# USB-PROG-UART.net
KiCad netlist of a schematic drawn in Altium Designer
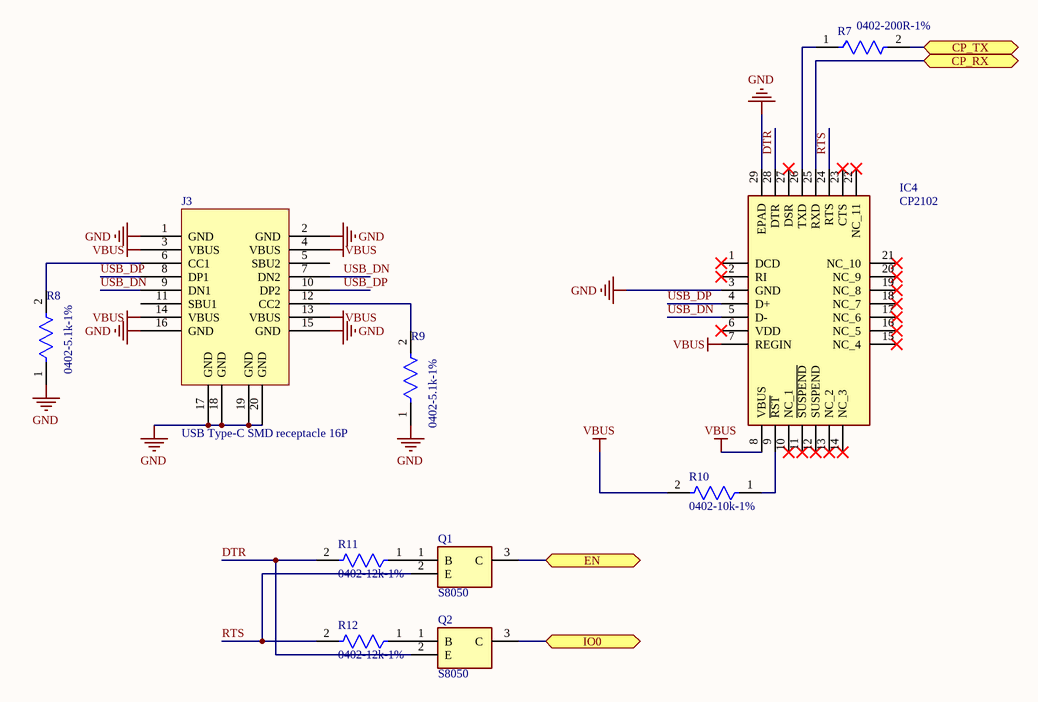
[diagram p0: USB-PROG-UART.SchDoc]

(export (version "E")
  (design (tool "Eeschema 10.0.6"))
  (components
    (comp (ref "IC4")
      (value "CP2102")
      (footprint "SamacSys:QFN50P500X500X100-29N-D")
      (description "Integrated Circuit")
      (fields (field (name "MOUSER PART NUMBER") "634-CP2102"))
      (libsource (lib "SamacSys") (part "CP2102"))
    )
    (comp (ref "J3")
      (value "USB Type-C SMD receptacle 16P")
      (footprint "USB Type-C SMD receptacle 16P")
      (libsource (lib "myLib") (part "USB Type-C SMD receptacle 16P"))
    )
    (comp (ref "Q1")
      (value "S8050")
      (footprint "SamacSys:SOT95P240X115-3N")
      (description "Transistor")
      (libsource (lib "SamacSys") (part "S8050"))
    )
    (comp (ref "Q2")
      (value "S8050")
      (footprint "SamacSys:SOT95P240X115-3N")
      (description "Transistor")
      (libsource (lib "*") (part "S8050"))
    )
    (comp (ref "R7")
      (value "0402-200R-1%")
      (footprint "FP-CRCW0402-e3-IPC_C")
      (description "RES Thick Film, 0Ω, 0.063W, 0402")
      (fields (field (name "TOLERANCE") "5%"))
      (libsource (lib "Altium Content Vault") (part "1029c3af85768c4190bb7ad29bc67b5"))
    )
    (comp (ref "R8")
      (value "0402-5.1k-1%")
      (footprint "FP-CRCW0402-e3-IPC_C")
      (description "RES Thick Film, 0Ω, 0.063W, 0402")
      (fields (field (name "TOLERANCE") "5%"))
      (libsource (lib "Altium Content Vault") (part "1029c3af85768c4190bb7ad29bc67b5"))
    )
    (comp (ref "R9")
      (value "0402-5.1k-1%")
      (footprint "FP-CRCW0402-e3-IPC_C")
      (description "RES Thick Film, 0Ω, 0.063W, 0402")
      (fields (field (name "TOLERANCE") "5%"))
      (libsource (lib "Altium Content Vault") (part "1029c3af85768c4190bb7ad29bc67b5"))
    )
    (comp (ref "R10")
      (value "0402-10k-1%")
      (footprint "FP-CRCW0402-e3-IPC_C")
      (description "RES Thick Film, 0Ω, 0.063W, 0402")
      (fields (field (name "TOLERANCE") "5%"))
      (libsource (lib "Altium Content Vault") (part "1029c3af85768c4190bb7ad29bc67b5"))
    )
    (comp (ref "R11")
      (value "0402-12k-1%")
      (footprint "FP-CRCW0402-e3-IPC_C")
      (description "RES Thick Film, 0Ω, 0.063W, 0402")
      (fields (field (name "TOLERANCE") "5%"))
      (libsource (lib "Altium Content Vault") (part "1029c3af85768c4190bb7ad29bc67b5"))
    )
    (comp (ref "R12")
      (value "0402-12k-1%")
      (footprint "FP-CRCW0402-e3-IPC_C")
      (description "RES Thick Film, 0Ω, 0.063W, 0402")
      (fields (field (name "TOLERANCE") "5%"))
      (libsource (lib "Altium Content Vault") (part "1029c3af85768c4190bb7ad29bc67b5"))
    )
  )
  (nets
    (net (code "1") (name "/CP_RX") (class "Default")
      (node (ref "IC4") (pin "25") (pinfunction "RXD_25") (pintype "passive"))
    )
    (net (code "2") (name "/CP_TX") (class "Default")
      (node (ref "R7") (pin "2") (pinfunction "2_2") (pintype "passive"))
    )
    (net (code "3") (name "/DTR") (class "Default")
      (node (ref "IC4") (pin "28") (pinfunction "DTR_28") (pintype "passive"))
      (node (ref "Q2") (pin "2") (pinfunction "E_2") (pintype "passive"))
      (node (ref "R11") (pin "2") (pinfunction "2_2") (pintype "passive"))
    )
    (net (code "4") (name "/EN") (class "Default")
      (node (ref "Q1") (pin "3") (pinfunction "C_3") (pintype "passive"))
    )
    (net (code "5") (name "/IO0") (class "Default")
      (node (ref "Q2") (pin "3") (pinfunction "C_3") (pintype "passive"))
    )
    (net (code "6") (name "/RTS") (class "Default")
      (node (ref "IC4") (pin "24") (pinfunction "RTS_24") (pintype "passive"))
      (node (ref "Q1") (pin "2") (pinfunction "E_2") (pintype "passive"))
      (node (ref "R12") (pin "2") (pinfunction "2_2") (pintype "passive"))
    )
    (net (code "7") (name "/USB_DN") (class "Default")
      (node (ref "IC4") (pin "5") (pinfunction "D-_5") (pintype "passive"))
      (node (ref "J3") (pin "7") (pinfunction "DN2_7") (pintype "passive"))
      (node (ref "J3") (pin "9") (pinfunction "DN1_9") (pintype "passive"))
    )
    (net (code "8") (name "/USB_DP") (class "Default")
      (node (ref "IC4") (pin "4") (pinfunction "D+_4") (pintype "passive"))
      (node (ref "J3") (pin "10") (pinfunction "DP2_10") (pintype "passive"))
      (node (ref "J3") (pin "8") (pinfunction "DP1_8") (pintype "passive"))
    )
    (net (code "9") (name "GND") (class "Default")
      (node (ref "IC4") (pin "29") (pinfunction "EPAD_29") (pintype "passive"))
      (node (ref "IC4") (pin "3") (pinfunction "GND_3") (pintype "passive"))
      (node (ref "J3") (pin "1") (pinfunction "GND_1") (pintype "passive"))
      (node (ref "J3") (pin "15") (pinfunction "GND_15") (pintype "passive"))
      (node (ref "J3") (pin "16") (pinfunction "GND_16") (pintype "passive"))
      (node (ref "J3") (pin "17") (pinfunction "GND_17") (pintype "passive"))
      (node (ref "J3") (pin "18") (pinfunction "GND_18") (pintype "passive"))
      (node (ref "J3") (pin "19") (pinfunction "GND_19") (pintype "passive"))
      (node (ref "J3") (pin "2") (pinfunction "GND_2") (pintype "passive"))
      (node (ref "J3") (pin "20") (pinfunction "GND_20") (pintype "passive"))
      (node (ref "R8") (pin "1") (pinfunction "1_1") (pintype "passive"))
      (node (ref "R9") (pin "1") (pinfunction "1_1") (pintype "passive"))
    )
    (net (code "10") (name "Net-(IC4-TXD)") (class "Default")
      (node (ref "IC4") (pin "26") (pinfunction "TXD_26") (pintype "passive"))
      (node (ref "R7") (pin "1") (pinfunction "1_1") (pintype "passive"))
    )
    (net (code "11") (name "Net-(IC4-~{RST})") (class "Default")
      (node (ref "IC4") (pin "9") (pinfunction "~{RST}_9") (pintype "passive"))
      (node (ref "R10") (pin "1") (pinfunction "1_1") (pintype "passive"))
    )
    (net (code "12") (name "Net-(J3-CC1)") (class "Default")
      (node (ref "J3") (pin "6") (pinfunction "CC1_6") (pintype "passive"))
      (node (ref "R8") (pin "2") (pinfunction "2_2") (pintype "passive"))
    )
    (net (code "13") (name "Net-(J3-CC2)") (class "Default")
      (node (ref "J3") (pin "12") (pinfunction "CC2_12") (pintype "passive"))
      (node (ref "R9") (pin "2") (pinfunction "2_2") (pintype "passive"))
    )
    (net (code "14") (name "Net-(Q1-B)") (class "Default")
      (node (ref "Q1") (pin "1") (pinfunction "B_1") (pintype "passive"))
      (node (ref "R11") (pin "1") (pinfunction "1_1") (pintype "passive"))
    )
    (net (code "15") (name "Net-(Q2-B)") (class "Default")
      (node (ref "Q2") (pin "1") (pinfunction "B_1") (pintype "passive"))
      (node (ref "R12") (pin "1") (pinfunction "1_1") (pintype "passive"))
    )
    (net (code "16") (name "VBUS") (class "Default")
      (node (ref "IC4") (pin "7") (pinfunction "REGIN_7") (pintype "passive"))
      (node (ref "IC4") (pin "8") (pinfunction "VBUS_8") (pintype "passive"))
      (node (ref "J3") (pin "13") (pinfunction "VBUS_13") (pintype "passive"))
      (node (ref "J3") (pin "14") (pinfunction "VBUS_14") (pintype "passive"))
      (node (ref "J3") (pin "3") (pinfunction "VBUS_3") (pintype "passive"))
      (node (ref "J3") (pin "4") (pinfunction "VBUS_4") (pintype "passive"))
      (node (ref "R10") (pin "2") (pinfunction "2_2") (pintype "passive"))
    )
    (net (code "17") (name "unconnected-(IC4-CTS-Pad23)") (class "Default")
      (node (ref "IC4") (pin "23") (pinfunction "CTS_23") (pintype "passive+no_connect"))
    )
    (net (code "18") (name "unconnected-(IC4-DCD-Pad1)") (class "Default")
      (node (ref "IC4") (pin "1") (pinfunction "DCD_1") (pintype "passive+no_connect"))
    )
    (net (code "19") (name "unconnected-(IC4-DSR-Pad27)") (class "Default")
      (node (ref "IC4") (pin "27") (pinfunction "DSR_27") (pintype "passive+no_connect"))
    )
    (net (code "20") (name "unconnected-(IC4-NC_1-Pad10)") (class "Default")
      (node (ref "IC4") (pin "10") (pinfunction "NC_1_10") (pintype "passive+no_connect"))
    )
    (net (code "21") (name "unconnected-(IC4-NC_2-Pad13)") (class "Default")
      (node (ref "IC4") (pin "13") (pinfunction "NC_2_13") (pintype "passive+no_connect"))
    )
    (net (code "22") (name "unconnected-(IC4-NC_3-Pad14)") (class "Default")
      (node (ref "IC4") (pin "14") (pinfunction "NC_3_14") (pintype "passive+no_connect"))
    )
    (net (code "23") (name "unconnected-(IC4-NC_4-Pad15)") (class "Default")
      (node (ref "IC4") (pin "15") (pinfunction "NC_4_15") (pintype "passive+no_connect"))
    )
    (net (code "24") (name "unconnected-(IC4-NC_5-Pad16)") (class "Default")
      (node (ref "IC4") (pin "16") (pinfunction "NC_5_16") (pintype "passive+no_connect"))
    )
    (net (code "25") (name "unconnected-(IC4-NC_6-Pad17)") (class "Default")
      (node (ref "IC4") (pin "17") (pinfunction "NC_6_17") (pintype "passive+no_connect"))
    )
    (net (code "26") (name "unconnected-(IC4-NC_7-Pad18)") (class "Default")
      (node (ref "IC4") (pin "18") (pinfunction "NC_7_18") (pintype "passive+no_connect"))
    )
    (net (code "27") (name "unconnected-(IC4-NC_8-Pad19)") (class "Default")
      (node (ref "IC4") (pin "19") (pinfunction "NC_8_19") (pintype "passive+no_connect"))
    )
    (net (code "28") (name "unconnected-(IC4-NC_9-Pad20)") (class "Default")
      (node (ref "IC4") (pin "20") (pinfunction "NC_9_20") (pintype "passive+no_connect"))
    )
    (net (code "29") (name "unconnected-(IC4-NC_10-Pad21)") (class "Default")
      (node (ref "IC4") (pin "21") (pinfunction "NC_10_21") (pintype "passive+no_connect"))
    )
    (net (code "30") (name "unconnected-(IC4-NC_11-Pad22)") (class "Default")
      (node (ref "IC4") (pin "22") (pinfunction "NC_11_22") (pintype "passive+no_connect"))
    )
    (net (code "31") (name "unconnected-(IC4-RI-Pad2)") (class "Default")
      (node (ref "IC4") (pin "2") (pinfunction "RI_2") (pintype "passive+no_connect"))
    )
    (net (code "32") (name "unconnected-(IC4-SUSPEND-Pad12)") (class "Default")
      (node (ref "IC4") (pin "12") (pinfunction "SUSPEND_12") (pintype "passive+no_connect"))
    )
    (net (code "33") (name "unconnected-(IC4-VDD-Pad6)") (class "Default")
      (node (ref "IC4") (pin "6") (pinfunction "VDD_6") (pintype "passive+no_connect"))
    )
    (net (code "34") (name "unconnected-(IC4-~{SUSPEND}-Pad11)") (class "Default")
      (node (ref "IC4") (pin "11") (pinfunction "~{SUSPEND}_11") (pintype "passive+no_connect"))
    )
    (net (code "35") (name "unconnected-(J3-SBU1-Pad11)") (class "Default")
      (node (ref "J3") (pin "11") (pinfunction "SBU1_11") (pintype "passive"))
    )
    (net (code "36") (name "unconnected-(J3-SBU2-Pad5)") (class "Default")
      (node (ref "J3") (pin "5") (pinfunction "SBU2_5") (pintype "passive"))
    )
  )
)
